# farmBot_schematic_v21.net
KiCad netlist of a schematic drawn in EAGLE
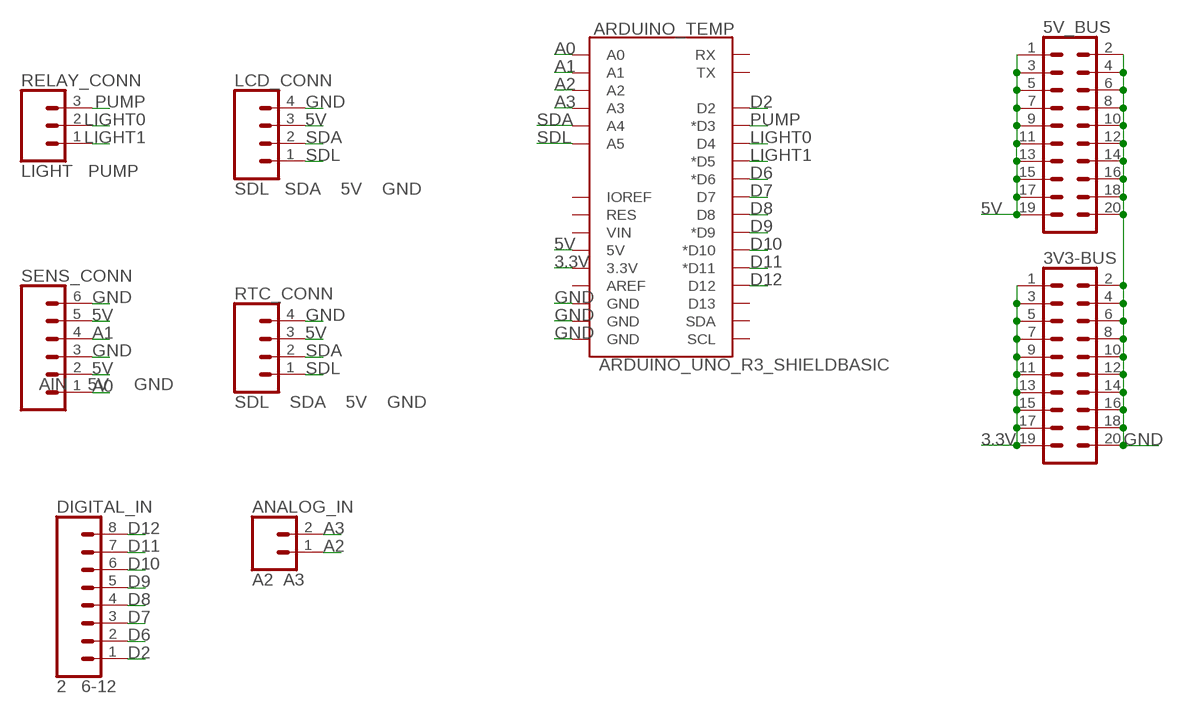
[diagram p0: schematic, sheet 1]

(export (version "E")
  (design (tool "Eeschema 10.0.6"))
  (components
    (comp (ref "3V3-BUS")
      (value "CONN_10X2")
      (footprint "eagle-import:2X10")
      (libsource (lib "eagle-import") (part "CONN_10X2"))
    )
    (comp (ref "5V_BUS")
      (value "CONN_10X2")
      (footprint "eagle-import:2X10")
      (libsource (lib "eagle-import") (part "CONN_10X2"))
    )
    (comp (ref "ANALOG_IN")
      (value "A2 A3")
      (footprint "eagle-import:1X02")
      (libsource (lib "eagle-import") (part "CONN_02"))
    )
    (comp (ref "ARDUINO_TEMP")
      (value "ARDUINO_UNO_R3_SHIELDBASIC")
      (footprint "eagle-import:UNO_R3_SHIELD")
      (libsource (lib "eagle-import") (part "ARDUINO_UNO_R3_SHIELDBASIC"))
    )
    (comp (ref "DIGITAL_IN")
      (value "2 6-12")
      (footprint "eagle-import:1X08")
      (libsource (lib "eagle-import") (part "CONN_08{dblquote}"))
    )
    (comp (ref "LCD_CONN")
      (value "SDL SDA 5V GND")
      (footprint "eagle-import:1X04")
      (libsource (lib "eagle-import") (part "CONN_04"))
    )
    (comp (ref "RELAY_CONN")
      (value "LIGHT PUMP")
      (footprint "eagle-import:1X03")
      (libsource (lib "eagle-import") (part "CONN_03"))
    )
    (comp (ref "RTC_CONN")
      (value "SDL SDA 5V GND")
      (footprint "eagle-import:1X04")
      (libsource (lib "eagle-import") (part "CONN_04"))
    )
    (comp (ref "SENS_CONN")
      (value "AIN 5V GND")
      (footprint "eagle-import:1X06")
      (libsource (lib "eagle-import") (part "CONN_06SILK_FEMALE_PTH"))
    )
  )
  (nets
    (net (code "1") (name "/3.3V") (class "Default")
      (node (ref "3V3-BUS") (pin "1") (pinfunction "1_1") (pintype "passive"))
      (node (ref "3V3-BUS") (pin "11") (pinfunction "11_11") (pintype "passive"))
      (node (ref "3V3-BUS") (pin "13") (pinfunction "13_13") (pintype "passive"))
      (node (ref "3V3-BUS") (pin "15") (pinfunction "15_15") (pintype "passive"))
      (node (ref "3V3-BUS") (pin "17") (pinfunction "17_17") (pintype "passive"))
      (node (ref "3V3-BUS") (pin "19") (pinfunction "19_19") (pintype "passive"))
      (node (ref "3V3-BUS") (pin "3") (pinfunction "3_3") (pintype "passive"))
      (node (ref "3V3-BUS") (pin "5") (pinfunction "5_5") (pintype "passive"))
      (node (ref "3V3-BUS") (pin "7") (pinfunction "7_7") (pintype "passive"))
      (node (ref "3V3-BUS") (pin "9") (pinfunction "9_9") (pintype "passive"))
      (node (ref "ARDUINO_TEMP") (pin "3.3V") (pinfunction "3.3V_3.3V") (pintype "bidirectional"))
    )
    (net (code "2") (name "/5V") (class "Default")
      (node (ref "5V_BUS") (pin "1") (pinfunction "1_1") (pintype "passive"))
      (node (ref "5V_BUS") (pin "11") (pinfunction "11_11") (pintype "passive"))
      (node (ref "5V_BUS") (pin "13") (pinfunction "13_13") (pintype "passive"))
      (node (ref "5V_BUS") (pin "15") (pinfunction "15_15") (pintype "passive"))
      (node (ref "5V_BUS") (pin "17") (pinfunction "17_17") (pintype "passive"))
      (node (ref "5V_BUS") (pin "19") (pinfunction "19_19") (pintype "passive"))
      (node (ref "5V_BUS") (pin "3") (pinfunction "3_3") (pintype "passive"))
      (node (ref "5V_BUS") (pin "5") (pinfunction "5_5") (pintype "passive"))
      (node (ref "5V_BUS") (pin "7") (pinfunction "7_7") (pintype "passive"))
      (node (ref "5V_BUS") (pin "9") (pinfunction "9_9") (pintype "passive"))
      (node (ref "ARDUINO_TEMP") (pin "5V") (pinfunction "5V_5V") (pintype "bidirectional"))
      (node (ref "LCD_CONN") (pin "3") (pinfunction "3_3") (pintype "passive"))
      (node (ref "RTC_CONN") (pin "3") (pinfunction "3_3") (pintype "passive"))
      (node (ref "SENS_CONN") (pin "2") (pinfunction "2_2") (pintype "passive"))
      (node (ref "SENS_CONN") (pin "5") (pinfunction "5_5") (pintype "passive"))
    )
    (net (code "3") (name "/A0") (class "Default")
      (node (ref "ARDUINO_TEMP") (pin "A0") (pinfunction "A0_A0") (pintype "bidirectional"))
      (node (ref "SENS_CONN") (pin "1") (pinfunction "1_1") (pintype "passive"))
    )
    (net (code "4") (name "/A1") (class "Default")
      (node (ref "ARDUINO_TEMP") (pin "A1") (pinfunction "A1_A1") (pintype "bidirectional"))
      (node (ref "SENS_CONN") (pin "4") (pinfunction "4_4") (pintype "passive"))
    )
    (net (code "5") (name "/A2") (class "Default")
      (node (ref "ANALOG_IN") (pin "1") (pinfunction "1_1") (pintype "passive"))
      (node (ref "ARDUINO_TEMP") (pin "A2") (pinfunction "A2_A2") (pintype "bidirectional"))
    )
    (net (code "6") (name "/A3") (class "Default")
      (node (ref "ANALOG_IN") (pin "2") (pinfunction "2_2") (pintype "passive"))
      (node (ref "ARDUINO_TEMP") (pin "A3") (pinfunction "A3_A3") (pintype "bidirectional"))
    )
    (net (code "7") (name "/D2") (class "Default")
      (node (ref "ARDUINO_TEMP") (pin "D2") (pinfunction "D2_D2") (pintype "bidirectional"))
      (node (ref "DIGITAL_IN") (pin "1") (pinfunction "1_1") (pintype "passive"))
    )
    (net (code "8") (name "/D6") (class "Default")
      (node (ref "ARDUINO_TEMP") (pin "D6") (pinfunction "*D6_D6") (pintype "bidirectional"))
      (node (ref "DIGITAL_IN") (pin "2") (pinfunction "2_2") (pintype "passive"))
    )
    (net (code "9") (name "/D7") (class "Default")
      (node (ref "ARDUINO_TEMP") (pin "D7") (pinfunction "D7_D7") (pintype "bidirectional"))
      (node (ref "DIGITAL_IN") (pin "3") (pinfunction "3_3") (pintype "passive"))
    )
    (net (code "10") (name "/D8") (class "Default")
      (node (ref "ARDUINO_TEMP") (pin "D8") (pinfunction "D8_D8") (pintype "bidirectional"))
      (node (ref "DIGITAL_IN") (pin "4") (pinfunction "4_4") (pintype "passive"))
    )
    (net (code "11") (name "/D9") (class "Default")
      (node (ref "ARDUINO_TEMP") (pin "D9") (pinfunction "*D9_D9") (pintype "bidirectional"))
      (node (ref "DIGITAL_IN") (pin "5") (pinfunction "5_5") (pintype "passive"))
    )
    (net (code "12") (name "/D10") (class "Default")
      (node (ref "ARDUINO_TEMP") (pin "D10") (pinfunction "*D10_D10") (pintype "bidirectional"))
      (node (ref "DIGITAL_IN") (pin "6") (pinfunction "6_6") (pintype "passive"))
    )
    (net (code "13") (name "/D11") (class "Default")
      (node (ref "ARDUINO_TEMP") (pin "D11") (pinfunction "*D11_D11") (pintype "bidirectional"))
      (node (ref "DIGITAL_IN") (pin "7") (pinfunction "7_7") (pintype "passive"))
    )
    (net (code "14") (name "/D12") (class "Default")
      (node (ref "ARDUINO_TEMP") (pin "D12") (pinfunction "D12_D12") (pintype "bidirectional"))
      (node (ref "DIGITAL_IN") (pin "8") (pinfunction "8_8") (pintype "passive"))
    )
    (net (code "15") (name "/GND") (class "Default")
      (node (ref "3V3-BUS") (pin "10") (pinfunction "10_10") (pintype "passive"))
      (node (ref "3V3-BUS") (pin "12") (pinfunction "12_12") (pintype "passive"))
      (node (ref "3V3-BUS") (pin "14") (pinfunction "14_14") (pintype "passive"))
      (node (ref "3V3-BUS") (pin "16") (pinfunction "16_16") (pintype "passive"))
      (node (ref "3V3-BUS") (pin "18") (pinfunction "18_18") (pintype "passive"))
      (node (ref "3V3-BUS") (pin "2") (pinfunction "2_2") (pintype "passive"))
      (node (ref "3V3-BUS") (pin "20") (pinfunction "20_20") (pintype "passive"))
      (node (ref "3V3-BUS") (pin "4") (pinfunction "4_4") (pintype "passive"))
      (node (ref "3V3-BUS") (pin "6") (pinfunction "6_6") (pintype "passive"))
      (node (ref "3V3-BUS") (pin "8") (pinfunction "8_8") (pintype "passive"))
      (node (ref "5V_BUS") (pin "10") (pinfunction "10_10") (pintype "passive"))
      (node (ref "5V_BUS") (pin "12") (pinfunction "12_12") (pintype "passive"))
      (node (ref "5V_BUS") (pin "14") (pinfunction "14_14") (pintype "passive"))
      (node (ref "5V_BUS") (pin "16") (pinfunction "16_16") (pintype "passive"))
      (node (ref "5V_BUS") (pin "18") (pinfunction "18_18") (pintype "passive"))
      (node (ref "5V_BUS") (pin "2") (pinfunction "2_2") (pintype "passive"))
      (node (ref "5V_BUS") (pin "20") (pinfunction "20_20") (pintype "passive"))
      (node (ref "5V_BUS") (pin "4") (pinfunction "4_4") (pintype "passive"))
      (node (ref "5V_BUS") (pin "6") (pinfunction "6_6") (pintype "passive"))
      (node (ref "5V_BUS") (pin "8") (pinfunction "8_8") (pintype "passive"))
      (node (ref "ARDUINO_TEMP") (pin "GND@0") (pinfunction "GND_GND@0") (pintype "bidirectional"))
      (node (ref "ARDUINO_TEMP") (pin "GND@1") (pinfunction "GND_GND@1") (pintype "bidirectional"))
      (node (ref "ARDUINO_TEMP") (pin "GND@2") (pinfunction "GND_GND@2") (pintype "bidirectional"))
      (node (ref "LCD_CONN") (pin "4") (pinfunction "4_4") (pintype "passive"))
      (node (ref "RTC_CONN") (pin "4") (pinfunction "4_4") (pintype "passive"))
      (node (ref "SENS_CONN") (pin "3") (pinfunction "3_3") (pintype "passive"))
      (node (ref "SENS_CONN") (pin "6") (pinfunction "6_6") (pintype "passive"))
    )
    (net (code "16") (name "/LIGHT0") (class "Default")
      (node (ref "ARDUINO_TEMP") (pin "D4") (pinfunction "D4_D4") (pintype "bidirectional"))
      (node (ref "RELAY_CONN") (pin "2") (pinfunction "2_2") (pintype "passive"))
    )
    (net (code "17") (name "/LIGHT1") (class "Default")
      (node (ref "ARDUINO_TEMP") (pin "D5") (pinfunction "*D5_D5") (pintype "bidirectional"))
      (node (ref "RELAY_CONN") (pin "1") (pinfunction "1_1") (pintype "passive"))
    )
    (net (code "18") (name "/PUMP") (class "Default")
      (node (ref "ARDUINO_TEMP") (pin "D3") (pinfunction "*D3_D3") (pintype "bidirectional"))
      (node (ref "RELAY_CONN") (pin "3") (pinfunction "3_3") (pintype "passive"))
    )
    (net (code "19") (name "/SDA") (class "Default")
      (node (ref "ARDUINO_TEMP") (pin "A4") (pinfunction "A4_A4") (pintype "bidirectional"))
      (node (ref "LCD_CONN") (pin "2") (pinfunction "2_2") (pintype "passive"))
      (node (ref "RTC_CONN") (pin "2") (pinfunction "2_2") (pintype "passive"))
    )
    (net (code "20") (name "/SDL") (class "Default")
      (node (ref "ARDUINO_TEMP") (pin "A5") (pinfunction "A5_A5") (pintype "bidirectional"))
      (node (ref "LCD_CONN") (pin "1") (pinfunction "1_1") (pintype "passive"))
      (node (ref "RTC_CONN") (pin "1") (pinfunction "1_1") (pintype "passive"))
    )
    (net (code "21") (name "unconnected-(ARDUINO_TEMP-PadAREF)") (class "Default")
      (node (ref "ARDUINO_TEMP") (pin "AREF") (pinfunction "AREF_AREF") (pintype "bidirectional"))
    )
    (net (code "22") (name "unconnected-(ARDUINO_TEMP-PadD13)") (class "Default")
      (node (ref "ARDUINO_TEMP") (pin "D13") (pinfunction "D13_D13") (pintype "bidirectional"))
    )
    (net (code "23") (name "unconnected-(ARDUINO_TEMP-PadIOREF)") (class "Default")
      (node (ref "ARDUINO_TEMP") (pin "IOREF") (pinfunction "IOREF_IOREF") (pintype "bidirectional"))
    )
    (net (code "24") (name "unconnected-(ARDUINO_TEMP-PadRES)") (class "Default")
      (node (ref "ARDUINO_TEMP") (pin "RES") (pinfunction "RES_RES") (pintype "bidirectional"))
    )
    (net (code "25") (name "unconnected-(ARDUINO_TEMP-PadRX)") (class "Default")
      (node (ref "ARDUINO_TEMP") (pin "RX") (pinfunction "RX_RX") (pintype "bidirectional"))
    )
    (net (code "26") (name "unconnected-(ARDUINO_TEMP-PadSCL)") (class "Default")
      (node (ref "ARDUINO_TEMP") (pin "SCL") (pinfunction "SCL_SCL") (pintype "bidirectional"))
    )
    (net (code "27") (name "unconnected-(ARDUINO_TEMP-PadSDA)") (class "Default")
      (node (ref "ARDUINO_TEMP") (pin "SDA") (pinfunction "SDA_SDA") (pintype "bidirectional"))
    )
    (net (code "28") (name "unconnected-(ARDUINO_TEMP-PadTX)") (class "Default")
      (node (ref "ARDUINO_TEMP") (pin "TX") (pinfunction "TX_TX") (pintype "bidirectional"))
    )
    (net (code "29") (name "unconnected-(ARDUINO_TEMP-PadVIN)") (class "Default")
      (node (ref "ARDUINO_TEMP") (pin "VIN") (pinfunction "VIN_VIN") (pintype "bidirectional"))
    )
  )
)
